# LED-board.net
KiCad netlist of a schematic drawn in EAGLE
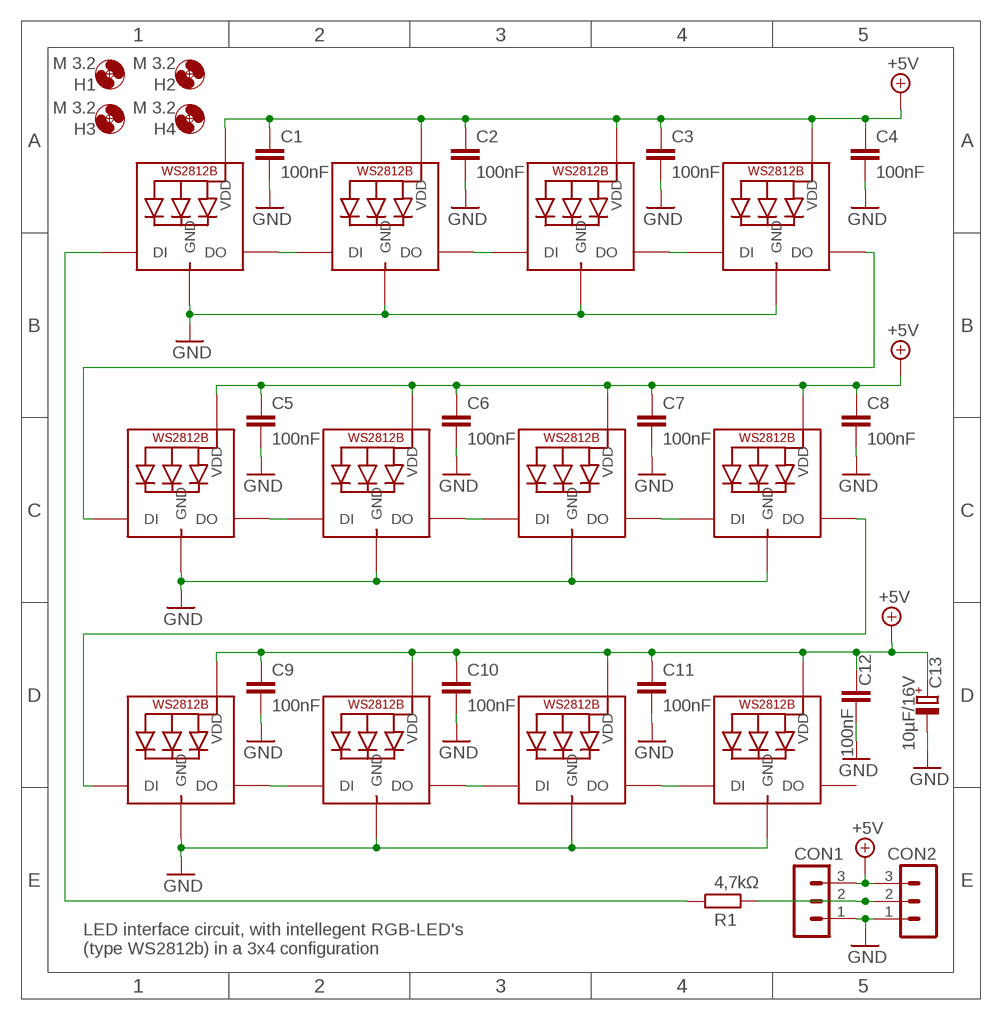
[diagram p0: schematic, sheet 1]

(export (version "E")
  (design (tool "Eeschema 10.0.6"))
  (components
    (comp (ref "C1")
      (value "100nF")
      (footprint "eagle-import:C050-025X075")
      (libsource (lib "eagle-import") (part "C-EU050-025X075"))
    )
    (comp (ref "C2")
      (value "100nF")
      (footprint "eagle-import:C050-025X075")
      (libsource (lib "eagle-import") (part "C-EU050-025X075"))
    )
    (comp (ref "C3")
      (value "100nF")
      (footprint "eagle-import:C050-025X075")
      (libsource (lib "eagle-import") (part "C-EU050-025X075"))
    )
    (comp (ref "C4")
      (value "100nF")
      (footprint "eagle-import:C050-025X075")
      (libsource (lib "eagle-import") (part "C-EU050-025X075"))
    )
    (comp (ref "C5")
      (value "100nF")
      (footprint "eagle-import:C050-025X075")
      (libsource (lib "eagle-import") (part "C-EU050-025X075"))
    )
    (comp (ref "C6")
      (value "100nF")
      (footprint "eagle-import:C050-025X075")
      (libsource (lib "eagle-import") (part "C-EU050-025X075"))
    )
    (comp (ref "C7")
      (value "100nF")
      (footprint "eagle-import:C050-025X075")
      (libsource (lib "eagle-import") (part "C-EU050-025X075"))
    )
    (comp (ref "C8")
      (value "100nF")
      (footprint "eagle-import:C050-025X075")
      (libsource (lib "eagle-import") (part "C-EU050-025X075"))
    )
    (comp (ref "C9")
      (value "100nF")
      (footprint "eagle-import:C050-025X075")
      (libsource (lib "eagle-import") (part "C-EU050-025X075"))
    )
    (comp (ref "C10")
      (value "100nF")
      (footprint "eagle-import:C050-025X075")
      (libsource (lib "eagle-import") (part "C-EU050-025X075"))
    )
    (comp (ref "C11")
      (value "100nF")
      (footprint "eagle-import:C050-025X075")
      (libsource (lib "eagle-import") (part "C-EU050-025X075"))
    )
    (comp (ref "C12")
      (value "100nF")
      (footprint "eagle-import:C050-025X075")
      (libsource (lib "eagle-import") (part "C-EU050-025X075"))
    )
    (comp (ref "C13")
      (value "10µF/16V")
      (footprint "eagle-import:E2-5")
      (libsource (lib "eagle-import") (part "CPOL-EUE2-5"))
    )
    (comp (ref "CON1")
      (value "MA03-1")
      (footprint "eagle-import:MA03-1")
      (libsource (lib "eagle-import") (part "MA03-1"))
    )
    (comp (ref "CON2")
      (value "MA03-1")
      (footprint "eagle-import:MA03-1")
      (libsource (lib "eagle-import") (part "MA03-1"))
    )
    (comp (ref "H1")
      (value "M 3.2")
      (footprint "eagle-import:3,2")
      (libsource (lib "eagle-import") (part "MOUNT-HOLE3.2"))
    )
    (comp (ref "H2")
      (value "M 3.2")
      (footprint "eagle-import:3,2")
      (libsource (lib "eagle-import") (part "MOUNT-HOLE3.2"))
    )
    (comp (ref "H3")
      (value "M 3.2")
      (footprint "eagle-import:3,2")
      (libsource (lib "eagle-import") (part "MOUNT-HOLE3.2"))
    )
    (comp (ref "H4")
      (value "M 3.2")
      (footprint "eagle-import:3,2")
      (libsource (lib "eagle-import") (part "MOUNT-HOLE3.2"))
    )
    (comp (ref "LED1")
      (value "WS2812B5050")
      (footprint "eagle-import:WS2812B")
      (libsource (lib "eagle-import") (part "WS2812B5050"))
    )
    (comp (ref "LED2")
      (value "WS2812B5050")
      (footprint "eagle-import:WS2812B")
      (libsource (lib "eagle-import") (part "WS2812B5050"))
    )
    (comp (ref "LED3")
      (value "WS2812B5050")
      (footprint "eagle-import:WS2812B")
      (libsource (lib "eagle-import") (part "WS2812B5050"))
    )
    (comp (ref "LED4")
      (value "WS2812B5050")
      (footprint "eagle-import:WS2812B")
      (libsource (lib "eagle-import") (part "WS2812B5050"))
    )
    (comp (ref "LED5")
      (value "WS2812B5050")
      (footprint "eagle-import:WS2812B")
      (libsource (lib "eagle-import") (part "WS2812B5050"))
    )
    (comp (ref "LED6")
      (value "WS2812B5050")
      (footprint "eagle-import:WS2812B")
      (libsource (lib "eagle-import") (part "WS2812B5050"))
    )
    (comp (ref "LED7")
      (value "WS2812B5050")
      (footprint "eagle-import:WS2812B")
      (libsource (lib "eagle-import") (part "WS2812B5050"))
    )
    (comp (ref "LED8")
      (value "WS2812B5050")
      (footprint "eagle-import:WS2812B")
      (libsource (lib "eagle-import") (part "WS2812B5050"))
    )
    (comp (ref "LED9")
      (value "WS2812B5050")
      (footprint "eagle-import:WS2812B")
      (libsource (lib "eagle-import") (part "WS2812B5050"))
    )
    (comp (ref "LED10")
      (value "WS2812B5050")
      (footprint "eagle-import:WS2812B")
      (libsource (lib "eagle-import") (part "WS2812B5050"))
    )
    (comp (ref "LED11")
      (value "WS2812B5050")
      (footprint "eagle-import:WS2812B")
      (libsource (lib "eagle-import") (part "WS2812B5050"))
    )
    (comp (ref "LED12")
      (value "WS2812B5050")
      (footprint "eagle-import:WS2812B")
      (libsource (lib "eagle-import") (part "WS2812B5050"))
    )
    (comp (ref "R1")
      (value "4,7kΩ")
      (footprint "eagle-import:0207_7")
      (libsource (lib "eagle-import") (part "R-EU_0207/7"))
    )
  )
  (nets
    (net (code "1") (name "+5V") (class "Default")
      (node (ref "C1") (pin "1") (pinfunction "1_1") (pintype "passive"))
      (node (ref "C10") (pin "1") (pinfunction "1_1") (pintype "passive"))
      (node (ref "C11") (pin "1") (pinfunction "1_1") (pintype "passive"))
      (node (ref "C12") (pin "1") (pinfunction "1_1") (pintype "passive"))
      (node (ref "C13") (pin "+") (pinfunction "+_+") (pintype "passive"))
      (node (ref "C2") (pin "1") (pinfunction "1_1") (pintype "passive"))
      (node (ref "C3") (pin "1") (pinfunction "1_1") (pintype "passive"))
      (node (ref "C4") (pin "1") (pinfunction "1_1") (pintype "passive"))
      (node (ref "C5") (pin "1") (pinfunction "1_1") (pintype "passive"))
      (node (ref "C6") (pin "1") (pinfunction "1_1") (pintype "passive"))
      (node (ref "C7") (pin "1") (pinfunction "1_1") (pintype "passive"))
      (node (ref "C8") (pin "1") (pinfunction "1_1") (pintype "passive"))
      (node (ref "C9") (pin "1") (pinfunction "1_1") (pintype "passive"))
      (node (ref "CON1") (pin "3") (pinfunction "3_3") (pintype "passive"))
      (node (ref "CON2") (pin "3") (pinfunction "3_3") (pintype "passive"))
      (node (ref "LED1") (pin "1-VDD") (pinfunction "VDD_1-VDD") (pintype "power_in"))
      (node (ref "LED10") (pin "1-VDD") (pinfunction "VDD_1-VDD") (pintype "power_in"))
      (node (ref "LED11") (pin "1-VDD") (pinfunction "VDD_1-VDD") (pintype "power_in"))
      (node (ref "LED12") (pin "1-VDD") (pinfunction "VDD_1-VDD") (pintype "power_in"))
      (node (ref "LED2") (pin "1-VDD") (pinfunction "VDD_1-VDD") (pintype "power_in"))
      (node (ref "LED3") (pin "1-VDD") (pinfunction "VDD_1-VDD") (pintype "power_in"))
      (node (ref "LED4") (pin "1-VDD") (pinfunction "VDD_1-VDD") (pintype "power_in"))
      (node (ref "LED5") (pin "1-VDD") (pinfunction "VDD_1-VDD") (pintype "power_in"))
      (node (ref "LED6") (pin "1-VDD") (pinfunction "VDD_1-VDD") (pintype "power_in"))
      (node (ref "LED7") (pin "1-VDD") (pinfunction "VDD_1-VDD") (pintype "power_in"))
      (node (ref "LED8") (pin "1-VDD") (pinfunction "VDD_1-VDD") (pintype "power_in"))
      (node (ref "LED9") (pin "1-VDD") (pinfunction "VDD_1-VDD") (pintype "power_in"))
    )
    (net (code "2") (name "GND") (class "Default")
      (node (ref "C1") (pin "2") (pinfunction "2_2") (pintype "passive"))
      (node (ref "C10") (pin "2") (pinfunction "2_2") (pintype "passive"))
      (node (ref "C11") (pin "2") (pinfunction "2_2") (pintype "passive"))
      (node (ref "C12") (pin "2") (pinfunction "2_2") (pintype "passive"))
      (node (ref "C13") (pin "-") (pinfunction "-_-") (pintype "passive"))
      (node (ref "C2") (pin "2") (pinfunction "2_2") (pintype "passive"))
      (node (ref "C3") (pin "2") (pinfunction "2_2") (pintype "passive"))
      (node (ref "C4") (pin "2") (pinfunction "2_2") (pintype "passive"))
      (node (ref "C5") (pin "2") (pinfunction "2_2") (pintype "passive"))
      (node (ref "C6") (pin "2") (pinfunction "2_2") (pintype "passive"))
      (node (ref "C7") (pin "2") (pinfunction "2_2") (pintype "passive"))
      (node (ref "C8") (pin "2") (pinfunction "2_2") (pintype "passive"))
      (node (ref "C9") (pin "2") (pinfunction "2_2") (pintype "passive"))
      (node (ref "CON1") (pin "1") (pinfunction "1_1") (pintype "passive"))
      (node (ref "CON2") (pin "1") (pinfunction "1_1") (pintype "passive"))
      (node (ref "LED1") (pin "3-GND") (pinfunction "GND_3-GND") (pintype "power_in"))
      (node (ref "LED10") (pin "3-GND") (pinfunction "GND_3-GND") (pintype "power_in"))
      (node (ref "LED11") (pin "3-GND") (pinfunction "GND_3-GND") (pintype "power_in"))
      (node (ref "LED12") (pin "3-GND") (pinfunction "GND_3-GND") (pintype "power_in"))
      (node (ref "LED2") (pin "3-GND") (pinfunction "GND_3-GND") (pintype "power_in"))
      (node (ref "LED3") (pin "3-GND") (pinfunction "GND_3-GND") (pintype "power_in"))
      (node (ref "LED4") (pin "3-GND") (pinfunction "GND_3-GND") (pintype "power_in"))
      (node (ref "LED5") (pin "3-GND") (pinfunction "GND_3-GND") (pintype "power_in"))
      (node (ref "LED6") (pin "3-GND") (pinfunction "GND_3-GND") (pintype "power_in"))
      (node (ref "LED7") (pin "3-GND") (pinfunction "GND_3-GND") (pintype "power_in"))
      (node (ref "LED8") (pin "3-GND") (pinfunction "GND_3-GND") (pintype "power_in"))
      (node (ref "LED9") (pin "3-GND") (pinfunction "GND_3-GND") (pintype "power_in"))
    )
    (net (code "3") (name "Net-(CON1-Pad2)") (class "Default")
      (node (ref "CON1") (pin "2") (pinfunction "2_2") (pintype "passive"))
      (node (ref "CON2") (pin "2") (pinfunction "2_2") (pintype "passive"))
      (node (ref "R1") (pin "2") (pinfunction "2_2") (pintype "passive"))
    )
    (net (code "4") (name "Net-(LED1-DI)") (class "Default")
      (node (ref "LED1") (pin "4-DIN") (pinfunction "DI_4-DIN") (pintype "input"))
      (node (ref "R1") (pin "1") (pinfunction "1_1") (pintype "passive"))
    )
    (net (code "5") (name "Net-(LED1-DO)") (class "Default")
      (node (ref "LED1") (pin "2-DOUT") (pinfunction "DO_2-DOUT") (pintype "output"))
      (node (ref "LED2") (pin "4-DIN") (pinfunction "DI_4-DIN") (pintype "input"))
    )
    (net (code "6") (name "Net-(LED2-DO)") (class "Default")
      (node (ref "LED2") (pin "2-DOUT") (pinfunction "DO_2-DOUT") (pintype "output"))
      (node (ref "LED3") (pin "4-DIN") (pinfunction "DI_4-DIN") (pintype "input"))
    )
    (net (code "7") (name "Net-(LED3-DO)") (class "Default")
      (node (ref "LED3") (pin "2-DOUT") (pinfunction "DO_2-DOUT") (pintype "output"))
      (node (ref "LED4") (pin "4-DIN") (pinfunction "DI_4-DIN") (pintype "input"))
    )
    (net (code "8") (name "Net-(LED4-DO)") (class "Default")
      (node (ref "LED4") (pin "2-DOUT") (pinfunction "DO_2-DOUT") (pintype "output"))
      (node (ref "LED5") (pin "4-DIN") (pinfunction "DI_4-DIN") (pintype "input"))
    )
    (net (code "9") (name "Net-(LED5-DO)") (class "Default")
      (node (ref "LED5") (pin "2-DOUT") (pinfunction "DO_2-DOUT") (pintype "output"))
      (node (ref "LED6") (pin "4-DIN") (pinfunction "DI_4-DIN") (pintype "input"))
    )
    (net (code "10") (name "Net-(LED6-DO)") (class "Default")
      (node (ref "LED6") (pin "2-DOUT") (pinfunction "DO_2-DOUT") (pintype "output"))
      (node (ref "LED7") (pin "4-DIN") (pinfunction "DI_4-DIN") (pintype "input"))
    )
    (net (code "11") (name "Net-(LED7-DO)") (class "Default")
      (node (ref "LED7") (pin "2-DOUT") (pinfunction "DO_2-DOUT") (pintype "output"))
      (node (ref "LED8") (pin "4-DIN") (pinfunction "DI_4-DIN") (pintype "input"))
    )
    (net (code "12") (name "Net-(LED8-DO)") (class "Default")
      (node (ref "LED8") (pin "2-DOUT") (pinfunction "DO_2-DOUT") (pintype "output"))
      (node (ref "LED9") (pin "4-DIN") (pinfunction "DI_4-DIN") (pintype "input"))
    )
    (net (code "13") (name "Net-(LED10-DI)") (class "Default")
      (node (ref "LED10") (pin "4-DIN") (pinfunction "DI_4-DIN") (pintype "input"))
      (node (ref "LED9") (pin "2-DOUT") (pinfunction "DO_2-DOUT") (pintype "output"))
    )
    (net (code "14") (name "Net-(LED10-DO)") (class "Default")
      (node (ref "LED10") (pin "2-DOUT") (pinfunction "DO_2-DOUT") (pintype "output"))
      (node (ref "LED11") (pin "4-DIN") (pinfunction "DI_4-DIN") (pintype "input"))
    )
    (net (code "15") (name "Net-(LED11-DO)") (class "Default")
      (node (ref "LED11") (pin "2-DOUT") (pinfunction "DO_2-DOUT") (pintype "output"))
      (node (ref "LED12") (pin "4-DIN") (pinfunction "DI_4-DIN") (pintype "input"))
    )
    (net (code "16") (name "unconnected-(LED12-DO-Pad2-DOUT)") (class "Default")
      (node (ref "LED12") (pin "2-DOUT") (pinfunction "DO_2-DOUT") (pintype "output"))
    )
  )
)
